# User_Interface.net
KiCad netlist of a schematic drawn in Altium Designer
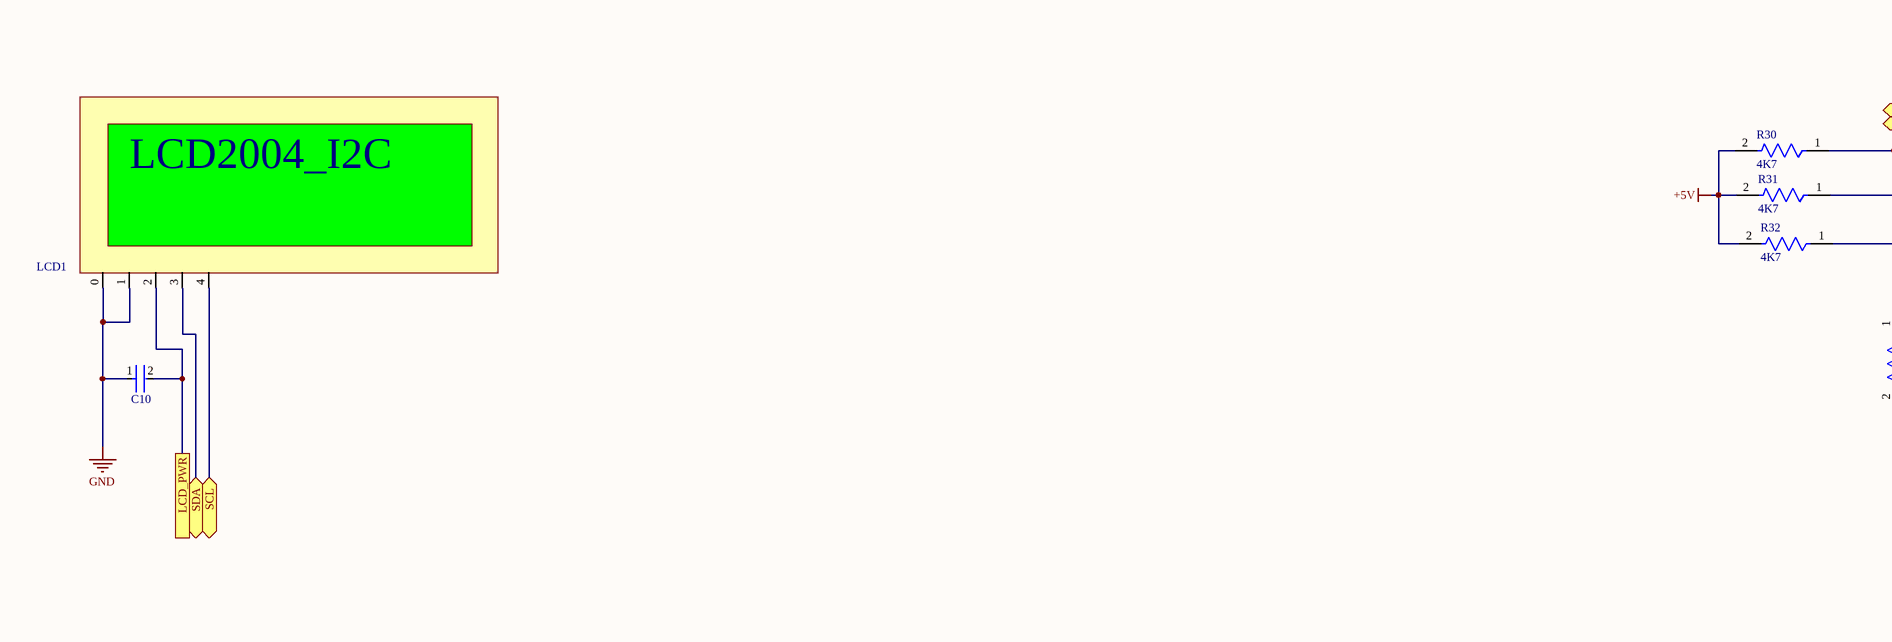
[diagram p0: User_Interface.SchDoc, top left]
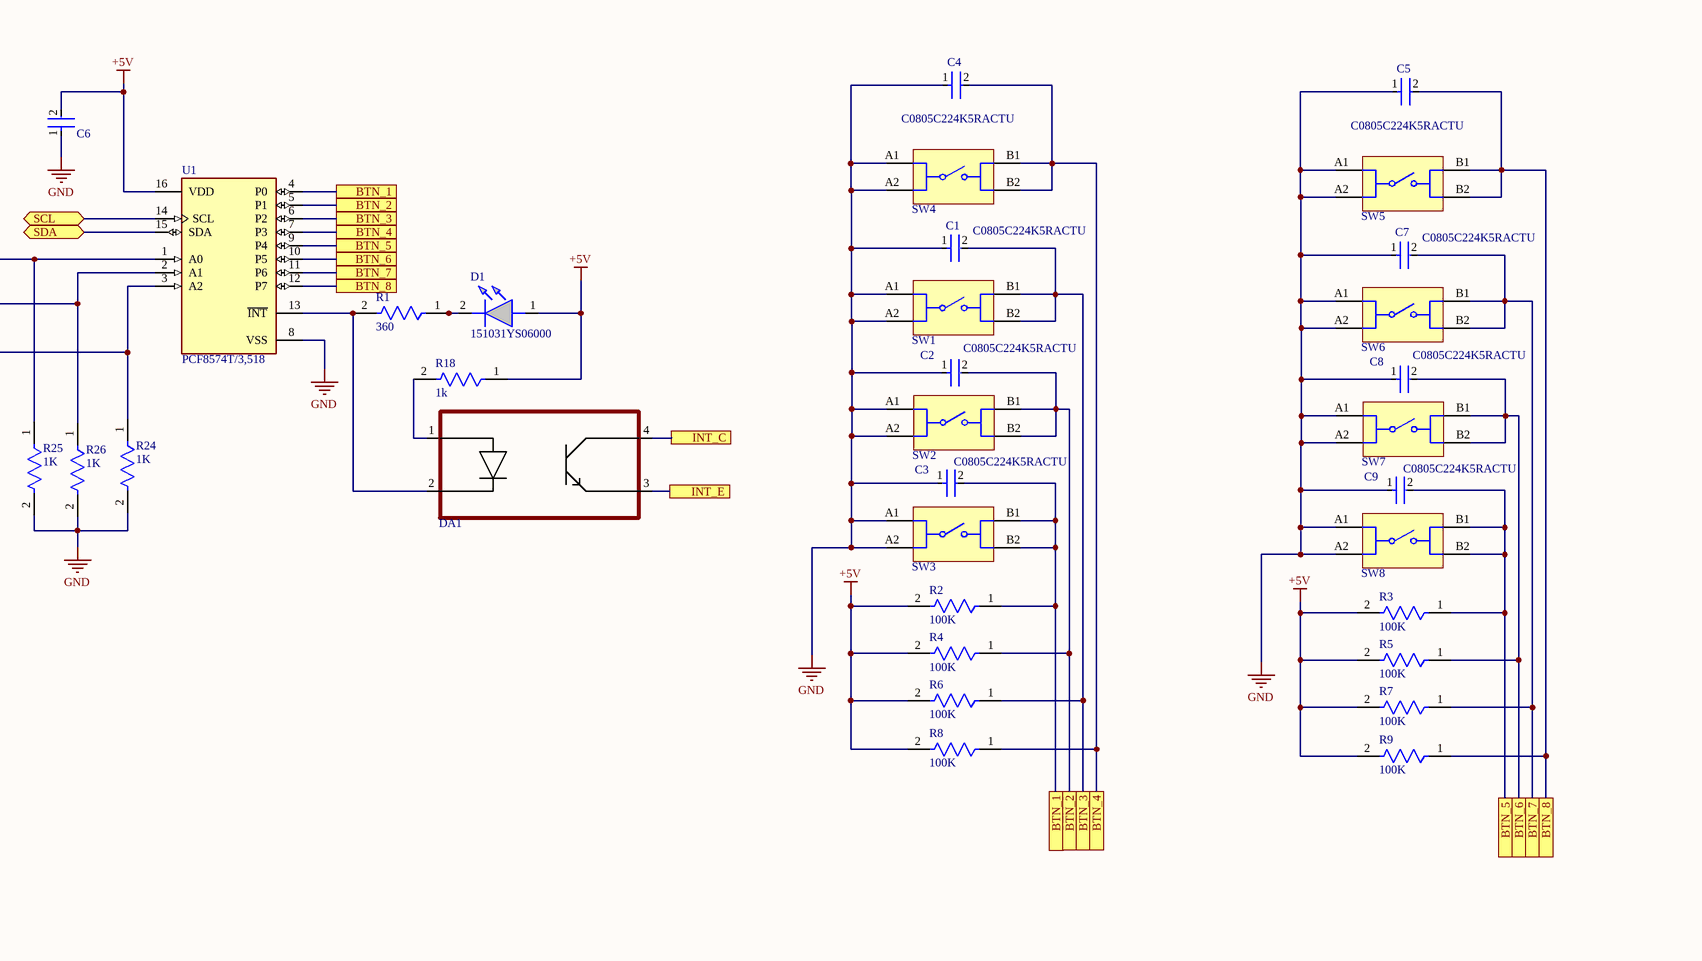
[diagram p1: User_Interface.SchDoc, top right]
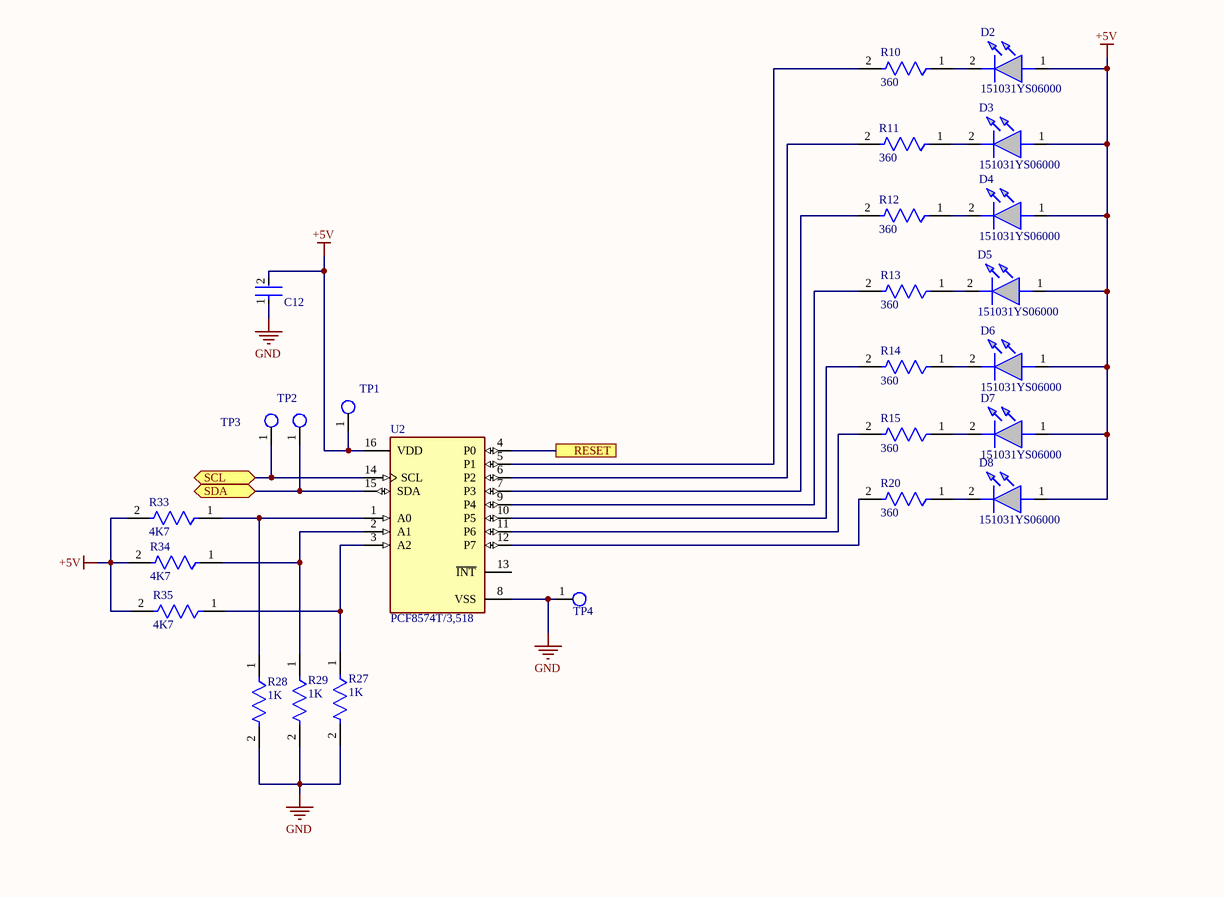
[diagram p2: User_Interface.SchDoc, bottom left]
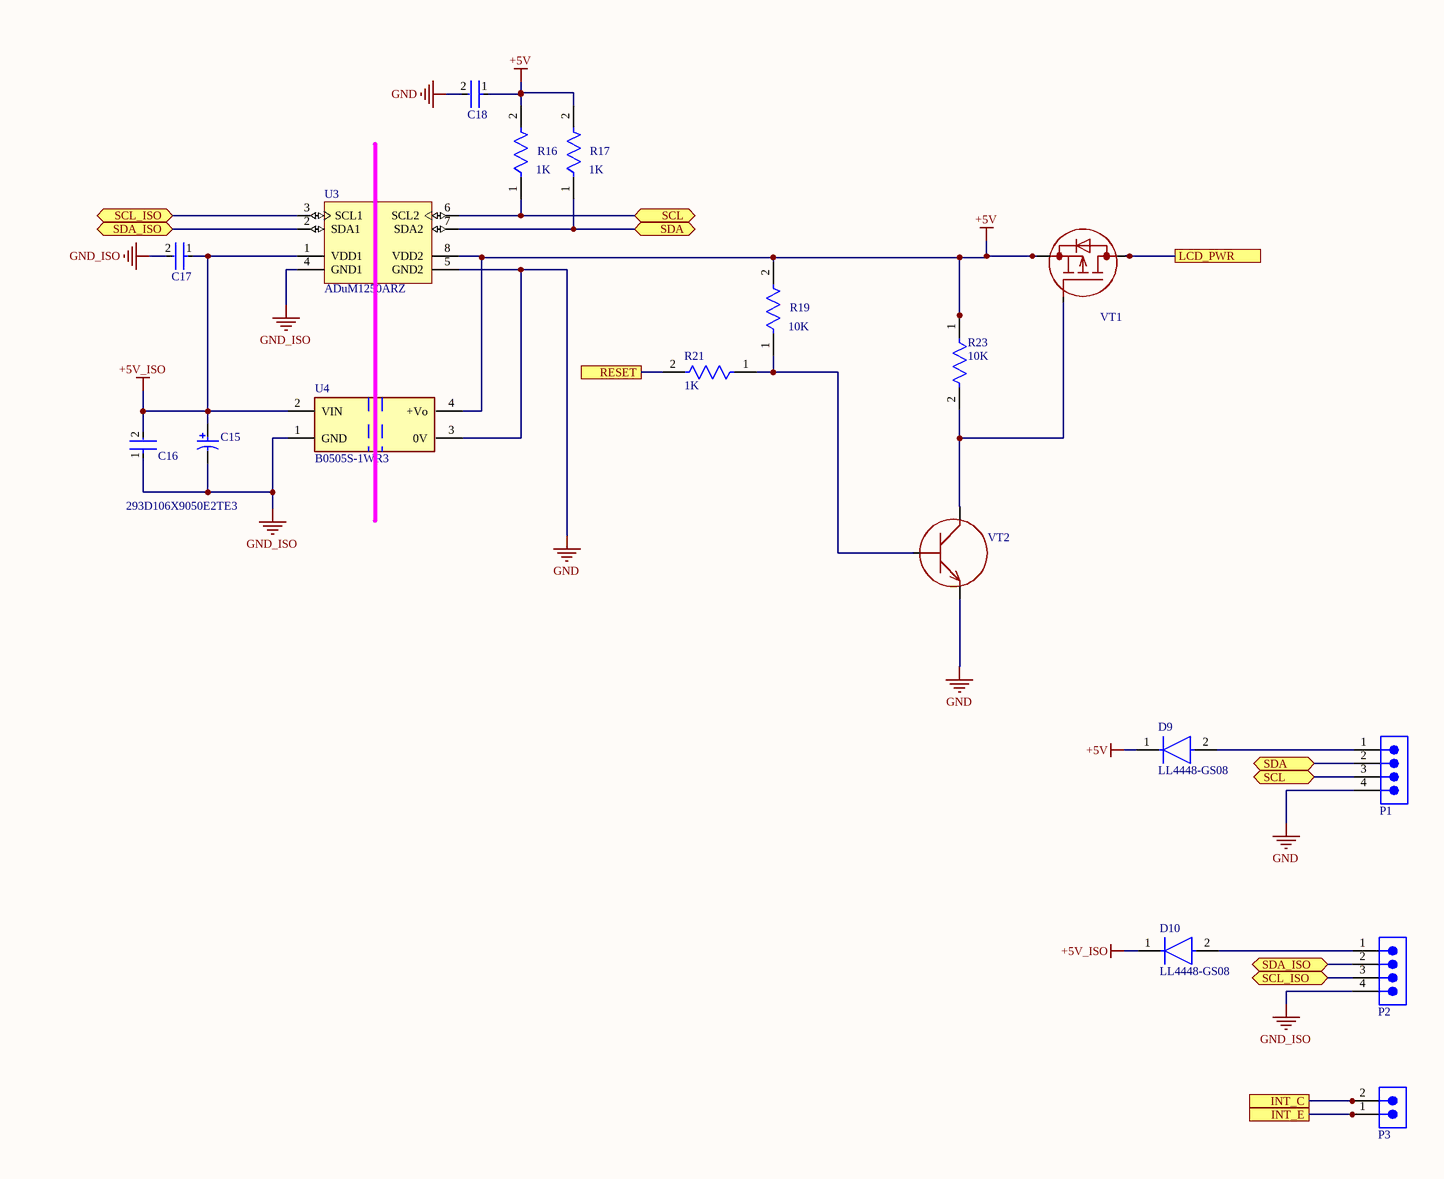
[diagram p3: User_Interface.SchDoc, bottom right]

(export (version "E")
  (design (tool "Eeschema 10.0.6"))
  (components
    (comp (ref "C1")
      (value "C0805C224K5RACTU")
      (footprint "FP-C0805C-DN-IPC_A")
      (description "CAP CER 0.22UF 50V X7R 0805")
      (fields
        (field (name "MANUFACTURER") "KEMET")
        (field (name "OCTOPART") "https://octopart.com/c0805c224k5ractu-kemet-144670")
      )
      (libsource (lib "Pasive_components") (part "CMP-1036-04552-2"))
    )
    (comp (ref "C2")
      (value "C0805C224K5RACTU")
      (footprint "FP-C0805C-DN-IPC_A")
      (description "CAP CER 0.22UF 50V X7R 0805")
      (fields
        (field (name "MANUFACTURER") "KEMET")
        (field (name "OCTOPART") "https://octopart.com/c0805c224k5ractu-kemet-144670")
      )
      (libsource (lib "Pasive_components") (part "CMP-1036-04552-2"))
    )
    (comp (ref "C3")
      (value "C0805C224K5RACTU")
      (footprint "FP-C0805C-DN-IPC_A")
      (description "CAP CER 0.22UF 50V X7R 0805")
      (fields
        (field (name "MANUFACTURER") "KEMET")
        (field (name "OCTOPART") "https://octopart.com/c0805c224k5ractu-kemet-144670")
      )
      (libsource (lib "Pasive_components") (part "CMP-1036-04552-2"))
    )
    (comp (ref "C4")
      (value "C0805C224K5RACTU")
      (footprint "FP-C0805C-DN-IPC_A")
      (description "CAP CER 0.22UF 50V X7R 0805")
      (fields
        (field (name "MANUFACTURER") "KEMET")
        (field (name "OCTOPART") "https://octopart.com/c0805c224k5ractu-kemet-144670")
      )
      (libsource (lib "Pasive_components") (part "CMP-1036-04552-2"))
    )
    (comp (ref "C5")
      (value "C0805C224K5RACTU")
      (footprint "FP-C0805C-DN-IPC_A")
      (description "CAP CER 0.22UF 50V X7R 0805")
      (fields
        (field (name "MANUFACTURER") "KEMET")
        (field (name "OCTOPART") "https://octopart.com/c0805c224k5ractu-kemet-144670")
      )
      (libsource (lib "Pasive_components") (part "CMP-1036-04552-2"))
    )
    (comp (ref "C6")
      (value "C0805C224K5RACTU")
      (footprint "FP-C0805C-DN-IPC_A")
      (description "CAP CER 0.22UF 50V X7R 0805")
      (fields
        (field (name "MANUFACTURER") "KEMET")
        (field (name "OCTOPART") "https://octopart.com/c0805c224k5ractu-kemet-144670")
      )
      (libsource (lib "Pasive_components") (part "CMP-1036-04552-2"))
    )
    (comp (ref "C7")
      (value "C0805C224K5RACTU")
      (footprint "FP-C0805C-DN-IPC_A")
      (description "CAP CER 0.22UF 50V X7R 0805")
      (fields
        (field (name "MANUFACTURER") "KEMET")
        (field (name "OCTOPART") "https://octopart.com/c0805c224k5ractu-kemet-144670")
      )
      (libsource (lib "Pasive_components") (part "CMP-1036-04552-2"))
    )
    (comp (ref "C8")
      (value "C0805C224K5RACTU")
      (footprint "FP-C0805C-DN-IPC_A")
      (description "CAP CER 0.22UF 50V X7R 0805")
      (fields
        (field (name "MANUFACTURER") "KEMET")
        (field (name "OCTOPART") "https://octopart.com/c0805c224k5ractu-kemet-144670")
      )
      (libsource (lib "Pasive_components") (part "CMP-1036-04552-2"))
    )
    (comp (ref "C9")
      (value "C0805C224K5RACTU")
      (footprint "FP-C0805C-DN-IPC_A")
      (description "CAP CER 0.22UF 50V X7R 0805")
      (fields
        (field (name "MANUFACTURER") "KEMET")
        (field (name "OCTOPART") "https://octopart.com/c0805c224k5ractu-kemet-144670")
      )
      (libsource (lib "Pasive_components") (part "CMP-1036-04552-2"))
    )
    (comp (ref "C10")
      (value "C0805C224K5RACTU")
      (footprint "FP-C0805C-DN-IPC_A")
      (description "CAP CER 0.22UF 50V X7R 0805")
      (fields
        (field (name "MANUFACTURER") "KEMET")
        (field (name "OCTOPART") "https://octopart.com/c0805c224k5ractu-kemet-144670")
      )
      (libsource (lib "Pasive_components") (part "CMP-1036-04552-2"))
    )
    (comp (ref "C12")
      (value "C0805C224K5RACTU")
      (footprint "FP-C0805C-DN-IPC_A")
      (description "CAP CER 0.22UF 50V X7R 0805")
      (fields
        (field (name "MANUFACTURER") "KEMET")
        (field (name "OCTOPART") "https://octopart.com/c0805c224k5ractu-kemet-144670")
      )
      (libsource (lib "Pasive_components") (part "CMP-1036-04552-2"))
    )
    (comp (ref "C15")
      (value "293D106X9050E2TE3")
      (footprint "VISH-293D-E_L")
      (fields (field (name "MANUFACTURER") "Vishay") (field (name "VOLTAGE") "50VDC"))
      (libsource (lib "Altium Content Vault") (part "CAP-P-2"))
    )
    (comp (ref "C16")
      (value "C0805C224K5RACTU")
      (footprint "FP-C0805C-DN-IPC_A")
      (description "CAP CER 0.22UF 50V X7R 0805")
      (fields
        (field (name "MANUFACTURER") "KEMET")
        (field (name "OCTOPART") "https://octopart.com/c0805c224k5ractu-kemet-144670")
      )
      (libsource (lib "Pasive_components") (part "CMP-1036-04552-2"))
    )
    (comp (ref "C17")
      (value "C0805C224K5RACTU")
      (footprint "FP-C0805C-DN-IPC_A")
      (description "CAP CER 0.22UF 50V X7R 0805")
      (fields
        (field (name "MANUFACTURER") "KEMET")
        (field (name "OCTOPART") "https://octopart.com/c0805c224k5ractu-kemet-144670")
      )
      (libsource (lib "Pasive_components") (part "CMP-1036-04552-2"))
    )
    (comp (ref "C18")
      (value "C0805C224K5RACTU")
      (footprint "FP-C0805C-DN-IPC_A")
      (description "CAP CER 0.22UF 50V X7R 0805")
      (fields
        (field (name "MANUFACTURER") "KEMET")
        (field (name "OCTOPART") "https://octopart.com/c0805c224k5ractu-kemet-144670")
      )
      (libsource (lib "Pasive_components") (part "CMP-1036-04552-2"))
    )
    (comp (ref "D1")
      (value "151031YS06000")
      (footprint "LED_BLUE")
      (description "WURTH ELEKTRONIK - 151031YS06000 - LED, Yellow, Through Hole, T-1 (3mm), 30 mA, 2 V, 590 nm")
      (fields (field (name "MOUSER PART NUMBER") "710-151031YS06000"))
      (libsource (lib "Optic-LED") (part "151031YS06000"))
    )
    (comp (ref "D2")
      (value "151031YS06000")
      (footprint "LED_GREEN")
      (description "WURTH ELEKTRONIK - 151031YS06000 - LED, Yellow, Through Hole, T-1 (3mm), 30 mA, 2 V, 590 nm")
      (fields (field (name "MOUSER PART NUMBER") "710-151031YS06000"))
      (libsource (lib "Optic-LED") (part "151031YS06000"))
    )
    (comp (ref "D3")
      (value "151031YS06000")
      (footprint "LED_GREEN")
      (description "WURTH ELEKTRONIK - 151031YS06000 - LED, Yellow, Through Hole, T-1 (3mm), 30 mA, 2 V, 590 nm")
      (fields (field (name "MOUSER PART NUMBER") "710-151031YS06000"))
      (libsource (lib "Optic-LED") (part "151031YS06000"))
    )
    (comp (ref "D4")
      (value "151031YS06000")
      (footprint "LED_GREEN")
      (description "WURTH ELEKTRONIK - 151031YS06000 - LED, Yellow, Through Hole, T-1 (3mm), 30 mA, 2 V, 590 nm")
      (fields (field (name "MOUSER PART NUMBER") "710-151031YS06000"))
      (libsource (lib "Optic-LED") (part "151031YS06000"))
    )
    (comp (ref "D5")
      (value "151031YS06000")
      (footprint "LED_GREEN")
      (description "WURTH ELEKTRONIK - 151031YS06000 - LED, Yellow, Through Hole, T-1 (3mm), 30 mA, 2 V, 590 nm")
      (fields (field (name "MOUSER PART NUMBER") "710-151031YS06000"))
      (libsource (lib "Optic-LED") (part "151031YS06000"))
    )
    (comp (ref "D6")
      (value "151031YS06000")
      (footprint "LED_GREEN")
      (description "WURTH ELEKTRONIK - 151031YS06000 - LED, Yellow, Through Hole, T-1 (3mm), 30 mA, 2 V, 590 nm")
      (fields (field (name "MOUSER PART NUMBER") "710-151031YS06000"))
      (libsource (lib "Optic-LED") (part "151031YS06000"))
    )
    (comp (ref "D7")
      (value "151031YS06000")
      (footprint "LED_GREEN")
      (description "WURTH ELEKTRONIK - 151031YS06000 - LED, Yellow, Through Hole, T-1 (3mm), 30 mA, 2 V, 590 nm")
      (fields (field (name "MOUSER PART NUMBER") "710-151031YS06000"))
      (libsource (lib "Optic-LED") (part "151031YS06000"))
    )
    (comp (ref "D8")
      (value "151031YS06000")
      (footprint "LED_GREEN")
      (description "WURTH ELEKTRONIK - 151031YS06000 - LED, Yellow, Through Hole, T-1 (3mm), 30 mA, 2 V, 590 nm")
      (fields (field (name "MOUSER PART NUMBER") "710-151031YS06000"))
      (libsource (lib "Optic-LED") (part "151031YS06000"))
    )
    (comp (ref "D9")
      (value "LL4448-GS08")
      (footprint "FP-6_560-5005_01-4-MFG")
      (description "DIODE GEN PURP 75V 150MA SOD80")
      (fields
        (field (name "MANUFACTURER") "Vishay Small Signal")
        (field (name "OCTOPART") "https://octopart.com/ll4448-gs08-vishay+small+signal-40886")
      )
      (libsource (lib "Altium Content Vault") (part "d7152d700b627762746794eb795d46e"))
    )
    (comp (ref "D10")
      (value "LL4448-GS08")
      (footprint "FP-6_560-5005_01-4-MFG")
      (description "DIODE GEN PURP 75V 150MA SOD80")
      (fields
        (field (name "MANUFACTURER") "Vishay Small Signal")
        (field (name "OCTOPART") "https://octopart.com/ll4448-gs08-vishay+small+signal-40886")
      )
      (libsource (lib "Altium Content Vault") (part "d7152d700b627762746794eb795d46e"))
    )
    (comp (ref "DA1") (value "PC817") (footprint "4-SMD") (libsource (lib "PC817") (part "PC817")))
    (comp (ref "LCD1")
      (value "2004_I2C")
      (footprint "LCD2004_I2C")
      (libsource (lib "LCD2004") (part "LCD2004_I2C"))
    )
    (comp (ref "P1")
      (value "61900411021")
      (footprint "61900411021")
      (description "WR-WTB THT Male Left Angled Bottom Locking Header, pitch 2.54mm, 4pins")
      (fields (field (name "MANUFACTURER") "Wurth Elektronik"))
      (libsource (lib "Altium_WR-WTB (rev22b)") (part "61900411021"))
    )
    (comp (ref "P2")
      (value "61900411021")
      (footprint "61900411021")
      (description "WR-WTB THT Male Left Angled Bottom Locking Header, pitch 2.54mm, 4pins")
      (fields (field (name "MANUFACTURER") "Wurth Elektronik"))
      (libsource (lib "Altium_WR-WTB (rev22b)") (part "61900411021"))
    )
    (comp (ref "P3")
      (value "61900211021")
      (footprint "61900211021")
      (description "WR-WTB THT Male Left Angled Bottom Locking Header, pitch 2.54mm, 2pins")
      (fields (field (name "MANUFACTURER") "Wurth Elektronik"))
      (libsource (lib "Altium_WR-WTB (rev22b)") (part "61900211021"))
    )
    (comp (ref "R1")
      (value "360")
      (footprint "FP-CRCW0805-e3-MFG")
      (description "RES Thick Film, 200Ω, 1%, 0.125W, 100ppm/°C, 0805")
      (fields (field (name "TOLERANCE") "1%"))
      (libsource (lib "Pasive_components") (part "CMP-2001-04908-2"))
    )
    (comp (ref "R2")
      (value "100K")
      (footprint "FP-CRCW0805-e3-MFG")
      (description "RES Thick Film, 100kΩ, 1%, 0.125W, 100ppm/°C, 0805")
      (fields (field (name "TOLERANCE") "1%"))
      (libsource (lib "Pasive_components") (part "CMP-2001-04908-2"))
    )
    (comp (ref "R3")
      (value "100K")
      (footprint "FP-CRCW0805-e3-MFG")
      (description "RES Thick Film, 100kΩ, 1%, 0.125W, 100ppm/°C, 0805")
      (fields (field (name "TOLERANCE") "1%"))
      (libsource (lib "Pasive_components") (part "CMP-2001-04908-2"))
    )
    (comp (ref "R4")
      (value "100K")
      (footprint "FP-CRCW0805-e3-MFG")
      (description "RES Thick Film, 100kΩ, 1%, 0.125W, 100ppm/°C, 0805")
      (fields (field (name "TOLERANCE") "1%"))
      (libsource (lib "Pasive_components") (part "CMP-2001-04908-2"))
    )
    (comp (ref "R5")
      (value "100K")
      (footprint "FP-CRCW0805-e3-MFG")
      (description "RES Thick Film, 100kΩ, 1%, 0.125W, 100ppm/°C, 0805")
      (fields (field (name "TOLERANCE") "1%"))
      (libsource (lib "Pasive_components") (part "CMP-2001-04908-2"))
    )
    (comp (ref "R6")
      (value "100K")
      (footprint "FP-CRCW0805-e3-MFG")
      (description "RES Thick Film, 100kΩ, 1%, 0.125W, 100ppm/°C, 0805")
      (fields (field (name "TOLERANCE") "1%"))
      (libsource (lib "Pasive_components") (part "CMP-2001-04908-2"))
    )
    (comp (ref "R7")
      (value "100K")
      (footprint "FP-CRCW0805-e3-MFG")
      (description "RES Thick Film, 100kΩ, 1%, 0.125W, 100ppm/°C, 0805")
      (fields (field (name "TOLERANCE") "1%"))
      (libsource (lib "Pasive_components") (part "CMP-2001-04908-2"))
    )
    (comp (ref "R8")
      (value "100K")
      (footprint "FP-CRCW0805-e3-MFG")
      (description "RES Thick Film, 100kΩ, 1%, 0.125W, 100ppm/°C, 0805")
      (fields (field (name "TOLERANCE") "1%"))
      (libsource (lib "Pasive_components") (part "CMP-2001-04908-2"))
    )
    (comp (ref "R9")
      (value "100K")
      (footprint "FP-CRCW0805-e3-MFG")
      (description "RES Thick Film, 100kΩ, 1%, 0.125W, 100ppm/°C, 0805")
      (fields (field (name "TOLERANCE") "1%"))
      (libsource (lib "Pasive_components") (part "CMP-2001-04908-2"))
    )
    (comp (ref "R10")
      (value "360")
      (footprint "FP-CRCW0805-e3-MFG")
      (description "RES Thick Film, 200Ω, 1%, 0.125W, 100ppm/°C, 0805")
      (fields (field (name "TOLERANCE") "1%"))
      (libsource (lib "Pasive_components") (part "CMP-2001-04908-2"))
    )
    (comp (ref "R11")
      (value "360")
      (footprint "FP-CRCW0805-e3-MFG")
      (description "RES Thick Film, 200Ω, 1%, 0.125W, 100ppm/°C, 0805")
      (fields (field (name "TOLERANCE") "1%"))
      (libsource (lib "Pasive_components") (part "CMP-2001-04908-2"))
    )
    (comp (ref "R12")
      (value "360")
      (footprint "FP-CRCW0805-e3-MFG")
      (description "RES Thick Film, 200Ω, 1%, 0.125W, 100ppm/°C, 0805")
      (fields (field (name "TOLERANCE") "1%"))
      (libsource (lib "Pasive_components") (part "CMP-2001-04908-2"))
    )
    (comp (ref "R13")
      (value "360")
      (footprint "FP-CRCW0805-e3-MFG")
      (description "RES Thick Film, 200Ω, 1%, 0.125W, 100ppm/°C, 0805")
      (fields (field (name "TOLERANCE") "1%"))
      (libsource (lib "Pasive_components") (part "CMP-2001-04908-2"))
    )
    (comp (ref "R14")
      (value "360")
      (footprint "FP-CRCW0805-e3-MFG")
      (description "RES Thick Film, 200Ω, 1%, 0.125W, 100ppm/°C, 0805")
      (fields (field (name "TOLERANCE") "1%"))
      (libsource (lib "Pasive_components") (part "CMP-2001-04908-2"))
    )
    (comp (ref "R15")
      (value "360")
      (footprint "FP-CRCW0805-e3-MFG")
      (description "RES Thick Film, 200Ω, 1%, 0.125W, 100ppm/°C, 0805")
      (fields (field (name "TOLERANCE") "1%"))
      (libsource (lib "Pasive_components") (part "CMP-2001-04908-2"))
    )
    (comp (ref "R16")
      (value "1K")
      (footprint "Vishay_CRCW0805-e3_IPC_A")
      (libsource (lib "Pasive_components") (part "CRCW08050000Z0EA"))
    )
    (comp (ref "R17")
      (value "1K")
      (footprint "Vishay_CRCW0805-e3_IPC_A")
      (libsource (lib "Pasive_components") (part "CRCW08050000Z0EA"))
    )
    (comp (ref "R18")
      (value "1k")
      (footprint "FP-CRCW0805-e3-MFG")
      (description "RES Thick Film, 200Ω, 1%, 0.125W, 100ppm/°C, 0805")
      (fields (field (name "TOLERANCE") "1%"))
      (libsource (lib "Pasive_components") (part "CMP-2001-04908-2"))
    )
    (comp (ref "R19")
      (value "10K")
      (footprint "Vishay_CRCW0805-e3_IPC_A")
      (libsource (lib "Pasive_components") (part "CRCW08050000Z0EA"))
    )
    (comp (ref "R20")
      (value "360")
      (footprint "FP-CRCW0805-e3-MFG")
      (description "RES Thick Film, 200Ω, 1%, 0.125W, 100ppm/°C, 0805")
      (fields (field (name "TOLERANCE") "1%"))
      (libsource (lib "Pasive_components") (part "CMP-2001-04908-2"))
    )
    (comp (ref "R21")
      (value "1K")
      (footprint "Vishay_CRCW0805-e3_IPC_A")
      (libsource (lib "Pasive_components") (part "CRCW08050000Z0EA"))
    )
    (comp (ref "R23")
      (value "10K")
      (footprint "Vishay_CRCW0805-e3_IPC_A")
      (libsource (lib "Pasive_components") (part "CRCW08050000Z0EA"))
    )
    (comp (ref "R24")
      (value "1K")
      (footprint "Vishay_CRCW0805-e3_IPC_A")
      (libsource (lib "Pasive_components") (part "CRCW08050000Z0EA"))
    )
    (comp (ref "R25")
      (value "1K")
      (footprint "Vishay_CRCW0805-e3_IPC_A")
      (libsource (lib "Pasive_components") (part "CRCW08050000Z0EA"))
    )
    (comp (ref "R26")
      (value "1K")
      (footprint "Vishay_CRCW0805-e3_IPC_A")
      (libsource (lib "Pasive_components") (part "CRCW08050000Z0EA"))
    )
    (comp (ref "R27")
      (value "1K")
      (footprint "Vishay_CRCW0805-e3_IPC_A")
      (libsource (lib "Pasive_components") (part "CRCW08050000Z0EA"))
    )
    (comp (ref "R28")
      (value "1K")
      (footprint "Vishay_CRCW0805-e3_IPC_A")
      (libsource (lib "Pasive_components") (part "CRCW08050000Z0EA"))
    )
    (comp (ref "R29")
      (value "1K")
      (footprint "Vishay_CRCW0805-e3_IPC_A")
      (libsource (lib "Pasive_components") (part "CRCW08050000Z0EA"))
    )
    (comp (ref "R30")
      (value "4K7")
      (footprint "Vishay_CRCW0805-e3_IPC_A")
      (libsource (lib "Pasive_components") (part "CRCW08050000Z0EA"))
    )
    (comp (ref "R31")
      (value "4K7")
      (footprint "Vishay_CRCW0805-e3_IPC_A")
      (libsource (lib "Pasive_components") (part "CRCW08050000Z0EA"))
    )
    (comp (ref "R32")
      (value "4K7")
      (footprint "Vishay_CRCW0805-e3_IPC_A")
      (libsource (lib "Pasive_components") (part "CRCW08050000Z0EA"))
    )
    (comp (ref "R33")
      (value "4K7")
      (footprint "Vishay_CRCW0805-e3_IPC_A")
      (libsource (lib "Pasive_components") (part "CRCW08050000Z0EA"))
    )
    (comp (ref "R34")
      (value "4K7")
      (footprint "Vishay_CRCW0805-e3_IPC_A")
      (libsource (lib "Pasive_components") (part "CRCW08050000Z0EA"))
    )
    (comp (ref "R35")
      (value "4K7")
      (footprint "Vishay_CRCW0805-e3_IPC_A")
      (libsource (lib "Pasive_components") (part "CRCW08050000Z0EA"))
    )
    (comp (ref "SW1")
      (value "430156043726")
      (footprint "4301x60437x6")
      (description "WS-TATV THT Tact Switch 6x6mm, SPST-NO, 12VDC, 50mA, 260g")
      (fields (field (name "MANUFACTURER") "Wurth Elektronik"))
      (libsource (lib "Altium_WS-TATV (rev22a)") (part "430156043726"))
    )
    (comp (ref "SW2")
      (value "430156043726")
      (footprint "4301x60437x6")
      (description "WS-TATV THT Tact Switch 6x6mm, SPST-NO, 12VDC, 50mA, 260g")
      (fields (field (name "MANUFACTURER") "Wurth Elektronik"))
      (libsource (lib "Altium_WS-TATV (rev22a)") (part "430156043726"))
    )
    (comp (ref "SW3")
      (value "430156043726")
      (footprint "4301x60437x6")
      (description "WS-TATV THT Tact Switch 6x6mm, SPST-NO, 12VDC, 50mA, 260g")
      (fields (field (name "MANUFACTURER") "Wurth Elektronik"))
      (libsource (lib "Altium_WS-TATV (rev22a)") (part "430156043726"))
    )
    (comp (ref "SW4")
      (value "430156043726")
      (footprint "4301x60437x6")
      (description "WS-TATV THT Tact Switch 6x6mm, SPST-NO, 12VDC, 50mA, 260g")
      (fields (field (name "MANUFACTURER") "Wurth Elektronik"))
      (libsource (lib "Altium_WS-TATV (rev22a)") (part "430156043726"))
    )
    (comp (ref "SW5")
      (value "430156043726")
      (footprint "4301x60437x6")
      (description "WS-TATV THT Tact Switch 6x6mm, SPST-NO, 12VDC, 50mA, 260g")
      (fields (field (name "MANUFACTURER") "Wurth Elektronik"))
      (libsource (lib "Altium_WS-TATV (rev22a)") (part "430156043726"))
    )
    (comp (ref "SW6")
      (value "430156043726")
      (footprint "4301x60437x6")
      (description "WS-TATV THT Tact Switch 6x6mm, SPST-NO, 12VDC, 50mA, 260g")
      (fields (field (name "MANUFACTURER") "Wurth Elektronik"))
      (libsource (lib "Altium_WS-TATV (rev22a)") (part "430156043726"))
    )
    (comp (ref "SW7")
      (value "430156043726")
      (footprint "4301x60437x6")
      (description "WS-TATV THT Tact Switch 6x6mm, SPST-NO, 12VDC, 50mA, 260g")
      (fields (field (name "MANUFACTURER") "Wurth Elektronik"))
      (libsource (lib "Altium_WS-TATV (rev22a)") (part "430156043726"))
    )
    (comp (ref "SW8")
      (value "430156043726")
      (footprint "4301x60437x6")
      (description "WS-TATV THT Tact Switch 6x6mm, SPST-NO, 12VDC, 50mA, 260g")
      (fields (field (name "MANUFACTURER") "Wurth Elektronik"))
      (libsource (lib "Altium_WS-TATV (rev22a)") (part "430156043726"))
    )
    (comp (ref "TP1")
      (value "Test_Point_PCB")
      (footprint "Test_Point")
      (description "Test_Point")
      (libsource (lib "Test_Point") (part "TP_PCB?"))
    )
    (comp (ref "TP2")
      (value "Test_Point_PCB")
      (footprint "Test_Point")
      (description "Test_Point")
      (libsource (lib "Test_Point") (part "TP_PCB?"))
    )
    (comp (ref "TP3")
      (value "Test_Point_PCB")
      (footprint "Test_Point")
      (description "Test_Point")
      (libsource (lib "Test_Point") (part "TP_PCB?"))
    )
    (comp (ref "TP4")
      (value "Test_Point_PCB")
      (footprint "Test_Point")
      (description "Test_Point")
      (libsource (lib "Test_Point") (part "TP_PCB?"))
    )
    (comp (ref "U1")
      (value "PCF8574T/3,518")
      (footprint "FP-SOT162-1-MFG")
      (description "IC I/O EXPANDER I2C 8B 16SOIC")
      (fields
        (field (name "MANUFACTURER") "NXP Semiconductors")
        (field (name "OCTOPART") "https://octopart.com/pcf8574t%2F3%2C518-nxp+semiconductors-10470852")
      )
      (libsource (lib "Altium Content Vault") (part "f7fde53ce59de981fb0b266a4e103eb"))
    )
    (comp (ref "U2")
      (value "PCF8574T/3,518")
      (footprint "FP-SOT162-1-MFG")
      (description "IC I/O EXPANDER I2C 8B 16SOIC")
      (fields
        (field (name "MANUFACTURER") "NXP Semiconductors")
        (field (name "OCTOPART") "https://octopart.com/pcf8574t%2F3%2C518-nxp+semiconductors-10470852")
      )
      (libsource (lib "Altium Content Vault") (part "f7fde53ce59de981fb0b266a4e103eb"))
    )
    (comp (ref "U3")
      (value "ADuM1250ARZ")
      (footprint "ADI-R-8_N")
      (description "Hot Swappable, Dual I2C Isolator, 3 to 5.5 V, -40 to 105 degC, 8-Pin SOIC (R-8), RoHS, Tube")
      (fields (field (name "GENERIC PART NUMBER") "ADUM1250"))
      (libsource (lib "ADUM1250-ARZ") (part "CMP-0534-00654-1"))
    )
    (comp (ref "U4")
      (value "B0505S-1WR3")
      (footprint "FP-B0505S-1WR3-MFG")
      (description "DC DC Converter 5V 1W")
      (libsource (lib "B0505S-1W") (part "B0505s-1W"))
    )
    (comp (ref "VT1")
      (value "MOSFET-P-CH")
      (footprint "SOT23-3")
      (libsource (lib "BSS84") (part "MOSFET-P-CH"))
    )
    (comp (ref "VT2") (value "BC847-BEC") (footprint "SOT23-3") (libsource (lib "BC8XX") (part "BC847-BEC")))
  )
  (nets
    (net (code "1") (name "+5V") (class "Default")
      (node (ref "C12") (pin "2") (pinfunction "2_2") (pintype "passive"))
      (node (ref "C18") (pin "1") (pinfunction "1_1") (pintype "passive"))
      (node (ref "C6") (pin "2") (pinfunction "2_2") (pintype "passive"))
      (node (ref "D1") (pin "1") (pinfunction "A_1") (pintype "passive"))
      (node (ref "D2") (pin "1") (pinfunction "A_1") (pintype "passive"))
      (node (ref "D3") (pin "1") (pinfunction "A_1") (pintype "passive"))
      (node (ref "D4") (pin "1") (pinfunction "A_1") (pintype "passive"))
      (node (ref "D5") (pin "1") (pinfunction "A_1") (pintype "passive"))
      (node (ref "D6") (pin "1") (pinfunction "A_1") (pintype "passive"))
      (node (ref "D7") (pin "1") (pinfunction "A_1") (pintype "passive"))
      (node (ref "D8") (pin "1") (pinfunction "A_1") (pintype "passive"))
      (node (ref "D9") (pin "1") (pinfunction "C_1") (pintype "passive"))
      (node (ref "R16") (pin "2") (pinfunction "2_2") (pintype "passive"))
      (node (ref "R17") (pin "2") (pinfunction "2_2") (pintype "passive"))
      (node (ref "R18") (pin "1") (pinfunction "1_1") (pintype "passive"))
      (node (ref "R19") (pin "2") (pinfunction "2_2") (pintype "passive"))
      (node (ref "R2") (pin "2") (pinfunction "2_2") (pintype "passive"))
      (node (ref "R23") (pin "1") (pinfunction "1_1") (pintype "passive"))
      (node (ref "R3") (pin "2") (pinfunction "2_2") (pintype "passive"))
      (node (ref "R30") (pin "2") (pinfunction "2_2") (pintype "passive"))
      (node (ref "R31") (pin "2") (pinfunction "2_2") (pintype "passive"))
      (node (ref "R32") (pin "2") (pinfunction "2_2") (pintype "passive"))
      (node (ref "R33") (pin "2") (pinfunction "2_2") (pintype "passive"))
      (node (ref "R34") (pin "2") (pinfunction "2_2") (pintype "passive"))
      (node (ref "R35") (pin "2") (pinfunction "2_2") (pintype "passive"))
      (node (ref "R4") (pin "2") (pinfunction "2_2") (pintype "passive"))
      (node (ref "R5") (pin "2") (pinfunction "2_2") (pintype "passive"))
      (node (ref "R6") (pin "2") (pinfunction "2_2") (pintype "passive"))
      (node (ref "R7") (pin "2") (pinfunction "2_2") (pintype "passive"))
      (node (ref "R8") (pin "2") (pinfunction "2_2") (pintype "passive"))
      (node (ref "R9") (pin "2") (pinfunction "2_2") (pintype "passive"))
      (node (ref "TP1") (pin "1") (pinfunction "G9_1") (pintype "passive"))
      (node (ref "U1") (pin "16") (pinfunction "VDD_16") (pintype "power_in"))
      (node (ref "U2") (pin "16") (pinfunction "VDD_16") (pintype "power_in"))
      (node (ref "U3") (pin "8") (pinfunction "VDD2_8") (pintype "power_in"))
      (node (ref "U4") (pin "4") (pinfunction "+Vo_4") (pintype "power_in"))
      (node (ref "VT1") (pin "2") (pinfunction "S_2") (pintype "passive"))
    )
    (net (code "2") (name "+5V_ISO") (class "Default")
      (node (ref "C15") (pin "1") (pinfunction "1_1") (pintype "passive"))
      (node (ref "C16") (pin "2") (pinfunction "2_2") (pintype "passive"))
      (node (ref "C17") (pin "1") (pinfunction "1_1") (pintype "passive"))
      (node (ref "D10") (pin "1") (pinfunction "C_1") (pintype "passive"))
      (node (ref "U3") (pin "1") (pinfunction "VDD1_1") (pintype "power_in"))
      (node (ref "U4") (pin "2") (pinfunction "VIN_2") (pintype "power_in"))
    )
    (net (code "3") (name "/BTN_1") (class "Default")
      (node (ref "C3") (pin "2") (pinfunction "2_2") (pintype "passive"))
      (node (ref "R2") (pin "1") (pinfunction "1_1") (pintype "passive"))
      (node (ref "SW3") (pin "B1") (pinfunction "B1_B1") (pintype "passive"))
      (node (ref "SW3") (pin "B2") (pinfunction "B2_B2") (pintype "passive"))
      (node (ref "U1") (pin "4") (pinfunction "P0_4") (pintype "bidirectional"))
    )
    (net (code "4") (name "/BTN_2") (class "Default")
      (node (ref "C2") (pin "2") (pinfunction "2_2") (pintype "passive"))
      (node (ref "R4") (pin "1") (pinfunction "1_1") (pintype "passive"))
      (node (ref "SW2") (pin "B1") (pinfunction "B1_B1") (pintype "passive"))
      (node (ref "SW2") (pin "B2") (pinfunction "B2_B2") (pintype "passive"))
      (node (ref "U1") (pin "5") (pinfunction "P1_5") (pintype "bidirectional"))
    )
    (net (code "5") (name "/BTN_3") (class "Default")
      (node (ref "C1") (pin "2") (pinfunction "2_2") (pintype "passive"))
      (node (ref "R6") (pin "1") (pinfunction "1_1") (pintype "passive"))
      (node (ref "SW1") (pin "B1") (pinfunction "B1_B1") (pintype "passive"))
      (node (ref "SW1") (pin "B2") (pinfunction "B2_B2") (pintype "passive"))
      (node (ref "U1") (pin "6") (pinfunction "P2_6") (pintype "bidirectional"))
    )
    (net (code "6") (name "/BTN_4") (class "Default")
      (node (ref "C4") (pin "2") (pinfunction "2_2") (pintype "passive"))
      (node (ref "R8") (pin "1") (pinfunction "1_1") (pintype "passive"))
      (node (ref "SW4") (pin "B1") (pinfunction "B1_B1") (pintype "passive"))
      (node (ref "SW4") (pin "B2") (pinfunction "B2_B2") (pintype "passive"))
      (node (ref "U1") (pin "7") (pinfunction "P3_7") (pintype "bidirectional"))
    )
    (net (code "7") (name "/BTN_5") (class "Default")
      (node (ref "C9") (pin "2") (pinfunction "2_2") (pintype "passive"))
      (node (ref "R3") (pin "1") (pinfunction "1_1") (pintype "passive"))
      (node (ref "SW8") (pin "B1") (pinfunction "B1_B1") (pintype "passive"))
      (node (ref "SW8") (pin "B2") (pinfunction "B2_B2") (pintype "passive"))
      (node (ref "U1") (pin "9") (pinfunction "P4_9") (pintype "bidirectional"))
    )
    (net (code "8") (name "/BTN_6") (class "Default")
      (node (ref "C8") (pin "2") (pinfunction "2_2") (pintype "passive"))
      (node (ref "R5") (pin "1") (pinfunction "1_1") (pintype "passive"))
      (node (ref "SW7") (pin "B1") (pinfunction "B1_B1") (pintype "passive"))
      (node (ref "SW7") (pin "B2") (pinfunction "B2_B2") (pintype "passive"))
      (node (ref "U1") (pin "10") (pinfunction "P5_10") (pintype "bidirectional"))
    )
    (net (code "9") (name "/BTN_7") (class "Default")
      (node (ref "C7") (pin "2") (pinfunction "2_2") (pintype "passive"))
      (node (ref "R7") (pin "1") (pinfunction "1_1") (pintype "passive"))
      (node (ref "SW6") (pin "B1") (pinfunction "B1_B1") (pintype "passive"))
      (node (ref "SW6") (pin "B2") (pinfunction "B2_B2") (pintype "passive"))
      (node (ref "U1") (pin "11") (pinfunction "P6_11") (pintype "bidirectional"))
    )
    (net (code "10") (name "/BTN_8") (class "Default")
      (node (ref "C5") (pin "2") (pinfunction "2_2") (pintype "passive"))
      (node (ref "R9") (pin "1") (pinfunction "1_1") (pintype "passive"))
      (node (ref "SW5") (pin "B1") (pinfunction "B1_B1") (pintype "passive"))
      (node (ref "SW5") (pin "B2") (pinfunction "B2_B2") (pintype "passive"))
      (node (ref "U1") (pin "12") (pinfunction "P7_12") (pintype "bidirectional"))
    )
    (net (code "11") (name "/INT_C") (class "Default")
      (node (ref "DA1") (pin "4") (pinfunction "COLLECTOR_4") (pintype "passive"))
      (node (ref "P3") (pin "2") (pinfunction "2_2") (pintype "passive"))
    )
    (net (code "12") (name "/INT_E") (class "Default")
      (node (ref "DA1") (pin "3") (pinfunction "EMITTER_3") (pintype "passive"))
      (node (ref "P3") (pin "1") (pinfunction "1_1") (pintype "passive"))
    )
    (net (code "13") (name "/LCD_PWR") (class "Default")
      (node (ref "C10") (pin "2") (pinfunction "2_2") (pintype "passive"))
      (node (ref "LCD1") (pin "2") (pinfunction "2_2") (pintype "passive"))
      (node (ref "VT1") (pin "3") (pinfunction "D_3") (pintype "passive"))
    )
    (net (code "14") (name "/RESET") (class "Default")
      (node (ref "R21") (pin "2") (pinfunction "2_2") (pintype "passive"))
      (node (ref "U2") (pin "4") (pinfunction "P0_4") (pintype "bidirectional"))
    )
    (net (code "15") (name "/SCL") (class "Default")
      (node (ref "LCD1") (pin "4") (pinfunction "4_4") (pintype "passive"))
      (node (ref "P1") (pin "3") (pinfunction "3_3") (pintype "passive"))
      (node (ref "R16") (pin "1") (pinfunction "1_1") (pintype "passive"))
      (node (ref "TP3") (pin "1") (pinfunction "G9_1") (pintype "passive"))
      (node (ref "U1") (pin "14") (pinfunction "SCL_14") (pintype "input"))
      (node (ref "U2") (pin "14") (pinfunction "SCL_14") (pintype "input"))
      (node (ref "U3") (pin "6") (pinfunction "SCL2_6") (pintype "bidirectional"))
    )
    (net (code "16") (name "/SCL_ISO") (class "Default")
      (node (ref "P2") (pin "3") (pinfunction "3_3") (pintype "passive"))
      (node (ref "U3") (pin "3") (pinfunction "SCL1_3") (pintype "bidirectional"))
    )
    (net (code "17") (name "/SDA") (class "Default")
      (node (ref "LCD1") (pin "3") (pinfunction "3_3") (pintype "passive"))
      (node (ref "P1") (pin "2") (pinfunction "2_2") (pintype "passive"))
      (node (ref "R17") (pin "1") (pinfunction "1_1") (pintype "passive"))
      (node (ref "TP2") (pin "1") (pinfunction "G9_1") (pintype "passive"))
      (node (ref "U1") (pin "15") (pinfunction "SDA_15") (pintype "bidirectional"))
      (node (ref "U2") (pin "15") (pinfunction "SDA_15") (pintype "bidirectional"))
      (node (ref "U3") (pin "7") (pinfunction "SDA2_7") (pintype "bidirectional"))
    )
    (net (code "18") (name "/SDA_ISO") (class "Default")
      (node (ref "P2") (pin "2") (pinfunction "2_2") (pintype "passive"))
      (node (ref "U3") (pin "2") (pinfunction "SDA1_2") (pintype "bidirectional"))
    )
    (net (code "19") (name "GND") (class "Default")
      (node (ref "C1") (pin "1") (pinfunction "1_1") (pintype "passive"))
      (node (ref "C10") (pin "1") (pinfunction "1_1") (pintype "passive"))
      (node (ref "C12") (pin "1") (pinfunction "1_1") (pintype "passive"))
      (node (ref "C18") (pin "2") (pinfunction "2_2") (pintype "passive"))
      (node (ref "C2") (pin "1") (pinfunction "1_1") (pintype "passive"))
      (node (ref "C3") (pin "1") (pinfunction "1_1") (pintype "passive"))
      (node (ref "C4") (pin "1") (pinfunction "1_1") (pintype "passive"))
      (node (ref "C5") (pin "1") (pinfunction "1_1") (pintype "passive"))
      (node (ref "C6") (pin "1") (pinfunction "1_1") (pintype "passive"))
      (node (ref "C7") (pin "1") (pinfunction "1_1") (pintype "passive"))
      (node (ref "C8") (pin "1") (pinfunction "1_1") (pintype "passive"))
      (node (ref "C9") (pin "1") (pinfunction "1_1") (pintype "passive"))
      (node (ref "LCD1") (pin "0") (pinfunction "0_0") (pintype "passive"))
      (node (ref "LCD1") (pin "1") (pinfunction "1_1") (pintype "passive"))
      (node (ref "P1") (pin "4") (pinfunction "4_4") (pintype "passive"))
      (node (ref "R24") (pin "2") (pinfunction "2_2") (pintype "passive"))
      (node (ref "R25") (pin "2") (pinfunction "2_2") (pintype "passive"))
      (node (ref "R26") (pin "2") (pinfunction "2_2") (pintype "passive"))
      (node (ref "R27") (pin "2") (pinfunction "2_2") (pintype "passive"))
      (node (ref "R28") (pin "2") (pinfunction "2_2") (pintype "passive"))
      (node (ref "R29") (pin "2") (pinfunction "2_2") (pintype "passive"))
      (node (ref "SW1") (pin "A1") (pinfunction "A1_A1") (pintype "passive"))
      (node (ref "SW1") (pin "A2") (pinfunction "A2_A2") (pintype "passive"))
      (node (ref "SW2") (pin "A1") (pinfunction "A1_A1") (pintype "passive"))
      (node (ref "SW2") (pin "A2") (pinfunction "A2_A2") (pintype "passive"))
      (node (ref "SW3") (pin "A1") (pinfunction "A1_A1") (pintype "passive"))
      (node (ref "SW3") (pin "A2") (pinfunction "A2_A2") (pintype "passive"))
      (node (ref "SW4") (pin "A1") (pinfunction "A1_A1") (pintype "passive"))
      (node (ref "SW4") (pin "A2") (pinfunction "A2_A2") (pintype "passive"))
      (node (ref "SW5") (pin "A1") (pinfunction "A1_A1") (pintype "passive"))
      (node (ref "SW5") (pin "A2") (pinfunction "A2_A2") (pintype "passive"))
      (node (ref "SW6") (pin "A1") (pinfunction "A1_A1") (pintype "passive"))
      (node (ref "SW6") (pin "A2") (pinfunction "A2_A2") (pintype "passive"))
      (node (ref "SW7") (pin "A1") (pinfunction "A1_A1") (pintype "passive"))
      (node (ref "SW7") (pin "A2") (pinfunction "A2_A2") (pintype "passive"))
      (node (ref "SW8") (pin "A1") (pinfunction "A1_A1") (pintype "passive"))
      (node (ref "SW8") (pin "A2") (pinfunction "A2_A2") (pintype "passive"))
      (node (ref "TP4") (pin "1") (pinfunction "G9_1") (pintype "passive"))
      (node (ref "U1") (pin "8") (pinfunction "VSS_8") (pintype "power_in"))
      (node (ref "U2") (pin "8") (pinfunction "VSS_8") (pintype "power_in"))
      (node (ref "U3") (pin "5") (pinfunction "GND2_5") (pintype "power_in"))
      (node (ref "U4") (pin "3") (pinfunction "0V_3") (pintype "power_in"))
      (node (ref "VT2") (pin "2") (pinfunction "E_2") (pintype "passive"))
    )
    (net (code "20") (name "GND_ISO") (class "Default")
      (node (ref "C15") (pin "2") (pinfunction "2_2") (pintype "passive"))
      (node (ref "C16") (pin "1") (pinfunction "1_1") (pintype "passive"))
      (node (ref "C17") (pin "2") (pinfunction "2_2") (pintype "passive"))
      (node (ref "P2") (pin "4") (pinfunction "4_4") (pintype "passive"))
      (node (ref "U3") (pin "4") (pinfunction "GND1_4") (pintype "power_in"))
      (node (ref "U4") (pin "1") (pinfunction "GND_1") (pintype "power_in"))
    )
    (net (code "21") (name "Net-(D1-K)") (class "Default")
      (node (ref "D1") (pin "2") (pinfunction "K_2") (pintype "passive"))
      (node (ref "R1") (pin "1") (pinfunction "1_1") (pintype "passive"))
    )
    (net (code "22") (name "Net-(D2-K)") (class "Default")
      (node (ref "D2") (pin "2") (pinfunction "K_2") (pintype "passive"))
      (node (ref "R10") (pin "1") (pinfunction "1_1") (pintype "passive"))
    )
    (net (code "23") (name "Net-(D3-K)") (class "Default")
      (node (ref "D3") (pin "2") (pinfunction "K_2") (pintype "passive"))
      (node (ref "R11") (pin "1") (pinfunction "1_1") (pintype "passive"))
    )
    (net (code "24") (name "Net-(D4-K)") (class "Default")
      (node (ref "D4") (pin "2") (pinfunction "K_2") (pintype "passive"))
      (node (ref "R12") (pin "1") (pinfunction "1_1") (pintype "passive"))
    )
    (net (code "25") (name "Net-(D5-K)") (class "Default")
      (node (ref "D5") (pin "2") (pinfunction "K_2") (pintype "passive"))
      (node (ref "R13") (pin "1") (pinfunction "1_1") (pintype "passive"))
    )
    (net (code "26") (name "Net-(D6-K)") (class "Default")
      (node (ref "D6") (pin "2") (pinfunction "K_2") (pintype "passive"))
      (node (ref "R14") (pin "1") (pinfunction "1_1") (pintype "passive"))
    )
    (net (code "27") (name "Net-(D7-K)") (class "Default")
      (node (ref "D7") (pin "2") (pinfunction "K_2") (pintype "passive"))
      (node (ref "R15") (pin "1") (pinfunction "1_1") (pintype "passive"))
    )
    (net (code "28") (name "Net-(D8-K)") (class "Default")
      (node (ref "D8") (pin "2") (pinfunction "K_2") (pintype "passive"))
      (node (ref "R20") (pin "1") (pinfunction "1_1") (pintype "passive"))
    )
    (net (code "29") (name "Net-(D9-A)") (class "Default")
      (node (ref "D9") (pin "2") (pinfunction "A_2") (pintype "passive"))
      (node (ref "P1") (pin "1") (pinfunction "1_1") (pintype "passive"))
    )
    (net (code "30") (name "Net-(D10-A)") (class "Default")
      (node (ref "D10") (pin "2") (pinfunction "A_2") (pintype "passive"))
      (node (ref "P2") (pin "1") (pinfunction "1_1") (pintype "passive"))
    )
    (net (code "31") (name "Net-(DA1-ANODE)") (class "Default")
      (node (ref "DA1") (pin "1") (pinfunction "ANODE_1") (pintype "passive"))
      (node (ref "R18") (pin "2") (pinfunction "2_2") (pintype "passive"))
    )
    (net (code "32") (name "Net-(DA1-CATHODE)") (class "Default")
      (node (ref "DA1") (pin "2") (pinfunction "CATHODE_2") (pintype "passive"))
      (node (ref "R1") (pin "2") (pinfunction "2_2") (pintype "passive"))
      (node (ref "U1") (pin "13") (pinfunction "~{INT}_13") (pintype "open_collector"))
    )
    (net (code "33") (name "Net-(U1-A0)") (class "Default")
      (node (ref "R25") (pin "1") (pinfunction "1_1") (pintype "passive"))
      (node (ref "R30") (pin "1") (pinfunction "1_1") (pintype "passive"))
      (node (ref "U1") (pin "1") (pinfunction "A0_1") (pintype "input"))
    )
    (net (code "34") (name "Net-(U1-A1)") (class "Default")
      (node (ref "R26") (pin "1") (pinfunction "1_1") (pintype "passive"))
      (node (ref "R31") (pin "1") (pinfunction "1_1") (pintype "passive"))
      (node (ref "U1") (pin "2") (pinfunction "A1_2") (pintype "input"))
    )
    (net (code "35") (name "Net-(U1-A2)") (class "Default")
      (node (ref "R24") (pin "1") (pinfunction "1_1") (pintype "passive"))
      (node (ref "R32") (pin "1") (pinfunction "1_1") (pintype "passive"))
      (node (ref "U1") (pin "3") (pinfunction "A2_3") (pintype "input"))
    )
    (net (code "36") (name "Net-(U2-A0)") (class "Default")
      (node (ref "R28") (pin "1") (pinfunction "1_1") (pintype "passive"))
      (node (ref "R33") (pin "1") (pinfunction "1_1") (pintype "passive"))
      (node (ref "U2") (pin "1") (pinfunction "A0_1") (pintype "input"))
    )
    (net (code "37") (name "Net-(U2-A1)") (class "Default")
      (node (ref "R29") (pin "1") (pinfunction "1_1") (pintype "passive"))
      (node (ref "R34") (pin "1") (pinfunction "1_1") (pintype "passive"))
      (node (ref "U2") (pin "2") (pinfunction "A1_2") (pintype "input"))
    )
    (net (code "38") (name "Net-(U2-A2)") (class "Default")
      (node (ref "R27") (pin "1") (pinfunction "1_1") (pintype "passive"))
      (node (ref "R35") (pin "1") (pinfunction "1_1") (pintype "passive"))
      (node (ref "U2") (pin "3") (pinfunction "A2_3") (pintype "input"))
    )
    (net (code "39") (name "Net-(U2-P1)") (class "Default")
      (node (ref "R10") (pin "2") (pinfunction "2_2") (pintype "passive"))
      (node (ref "U2") (pin "5") (pinfunction "P1_5") (pintype "bidirectional"))
    )
    (net (code "40") (name "Net-(U2-P2)") (class "Default")
      (node (ref "R11") (pin "2") (pinfunction "2_2") (pintype "passive"))
      (node (ref "U2") (pin "6") (pinfunction "P2_6") (pintype "bidirectional"))
    )
    (net (code "41") (name "Net-(U2-P3)") (class "Default")
      (node (ref "R12") (pin "2") (pinfunction "2_2") (pintype "passive"))
      (node (ref "U2") (pin "7") (pinfunction "P3_7") (pintype "bidirectional"))
    )
    (net (code "42") (name "Net-(U2-P4)") (class "Default")
      (node (ref "R13") (pin "2") (pinfunction "2_2") (pintype "passive"))
      (node (ref "U2") (pin "9") (pinfunction "P4_9") (pintype "bidirectional"))
    )
    (net (code "43") (name "Net-(U2-P5)") (class "Default")
      (node (ref "R14") (pin "2") (pinfunction "2_2") (pintype "passive"))
      (node (ref "U2") (pin "10") (pinfunction "P5_10") (pintype "bidirectional"))
    )
    (net (code "44") (name "Net-(U2-P6)") (class "Default")
      (node (ref "R15") (pin "2") (pinfunction "2_2") (pintype "passive"))
      (node (ref "U2") (pin "11") (pinfunction "P6_11") (pintype "bidirectional"))
    )
    (net (code "45") (name "Net-(U2-P7)") (class "Default")
      (node (ref "R20") (pin "2") (pinfunction "2_2") (pintype "passive"))
      (node (ref "U2") (pin "12") (pinfunction "P7_12") (pintype "bidirectional"))
    )
    (net (code "46") (name "Net-(VT1-G)") (class "Default")
      (node (ref "R23") (pin "2") (pinfunction "2_2") (pintype "passive"))
      (node (ref "VT1") (pin "1") (pinfunction "G_1") (pintype "passive"))
      (node (ref "VT2") (pin "3") (pinfunction "C_3") (pintype "passive"))
    )
    (net (code "47") (name "Net-(VT2-B)") (class "Default")
      (node (ref "R19") (pin "1") (pinfunction "1_1") (pintype "passive"))
      (node (ref "R21") (pin "1") (pinfunction "1_1") (pintype "passive"))
      (node (ref "VT2") (pin "1") (pinfunction "B_1") (pintype "passive"))
    )
    (net (code "48") (name "unconnected-(U2-~{INT}-Pad13)") (class "Default")
      (node (ref "U2") (pin "13") (pinfunction "~{INT}_13") (pintype "open_collector"))
    )
  )
)
